# DEVELOPMENT-BOARD-PIC16F887.net
KiCad netlist of a schematic drawn in EasyEDA Pro
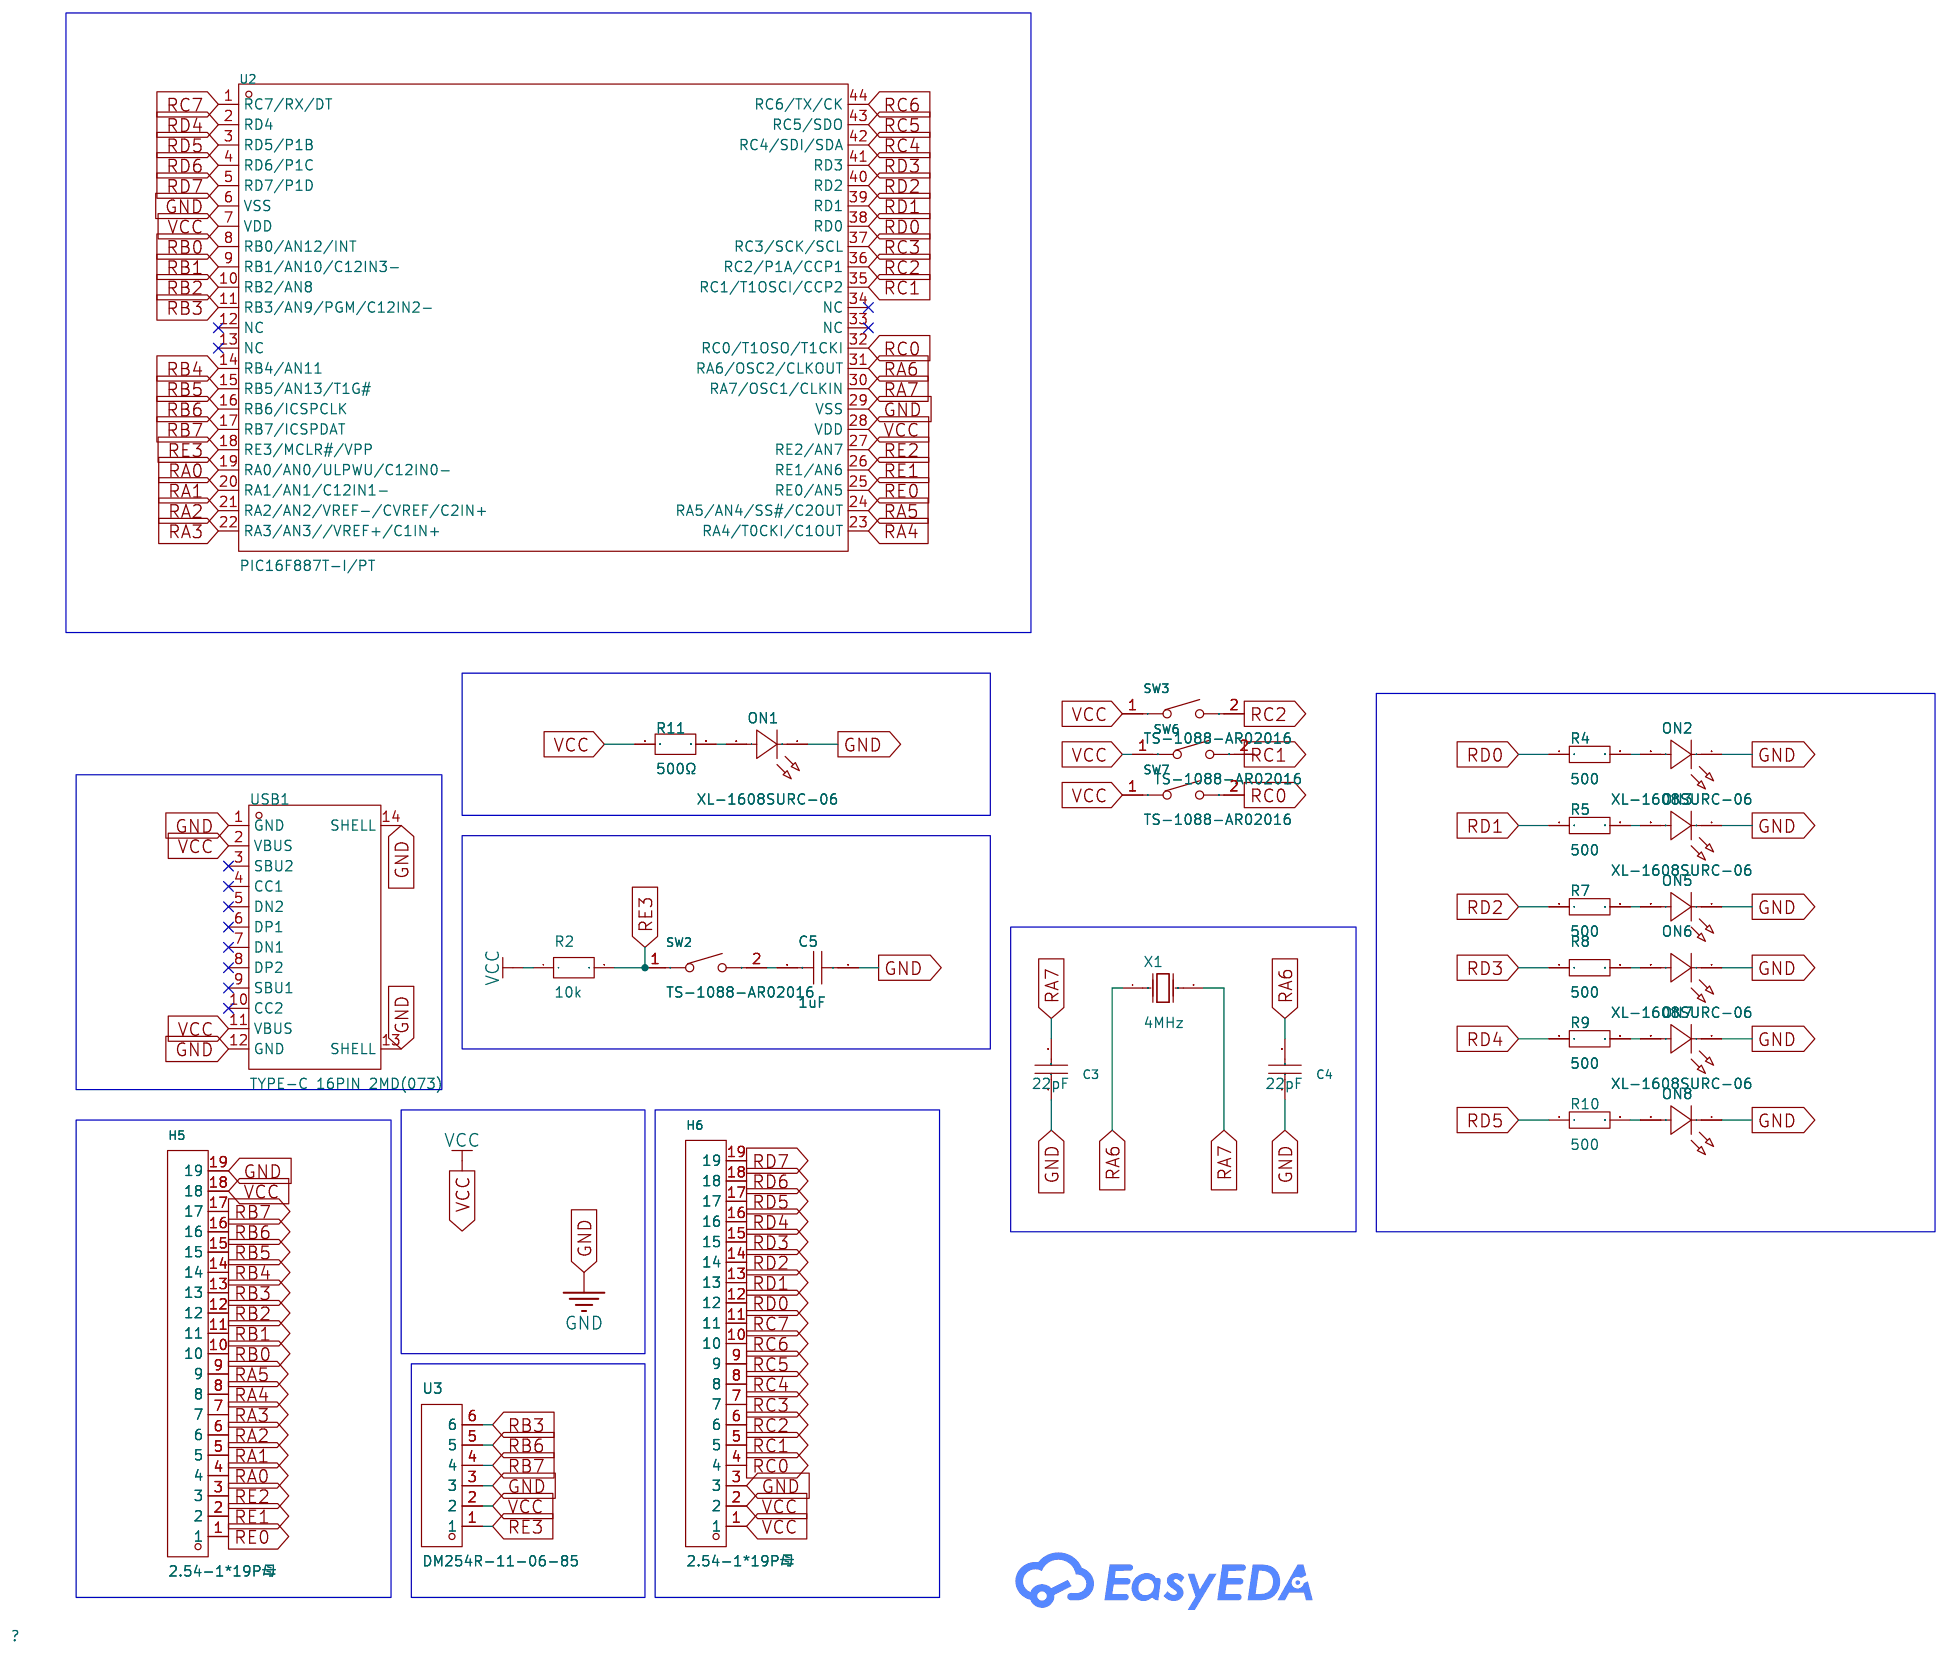
[diagram p0: schematic sheet]

(export (version "E")
  (design (tool "Eeschema 10.0.6"))
  (components
    (comp (ref "C3")
      (value "22pF")
      (footprint "easyedapro:C0402")
      (fields
        (field (name "Manufacturer Part") "CC0402JRNPO9BN150")
        (field (name "Manufacturer") "YAGEO(国巨)")
      )
      (libsource (lib "easyedapro") (part "CC0402JRNPO9BN150"))
    )
    (comp (ref "C4")
      (value "22pF")
      (footprint "easyedapro:C0402")
      (fields
        (field (name "Manufacturer Part") "CC0402JRNPO9BN150")
        (field (name "Manufacturer") "YAGEO(国巨)")
      )
      (libsource (lib "easyedapro") (part "CC0402JRNPO9BN150"))
    )
    (comp (ref "C5")
      (value "1uF")
      (footprint "easyedapro:C0603")
      (fields
        (field (name "Manufacturer Part") "CL10A105KB8NNNC")
        (field (name "Manufacturer") "SAMSUNG(三星)")
      )
      (libsource (lib "easyedapro") (part "CL10A105KB8NNNC"))
    )
    (comp (ref "H5")
      (value "2.54-1*19P母")
      (footprint "easyedapro:HDR-TH_19P-P2.54-V-F")
      (fields (field (name "Manufacturer") "BOOMELE(博穆精密)"))
      (libsource (lib "easyedapro") (part "2.54-1*19P母"))
    )
    (comp (ref "H6")
      (value "2.54-1*19P母")
      (footprint "easyedapro:HDR-TH_19P-P2.54-V-F")
      (fields (field (name "Manufacturer") "BOOMELE(博穆精密)"))
      (libsource (lib "easyedapro") (part "2.54-1*19P母"))
    )
    (comp (ref "ON1")
      (value "XL-1608SURC-06")
      (footprint "easyedapro:LED0603-RD_RED")
      (fields (field (name "Manufacturer") "XINGLIGHT(成兴光)"))
      (libsource (lib "easyedapro") (part "XL-1608SURC-06"))
    )
    (comp (ref "ON2")
      (value "XL-1608SURC-06")
      (footprint "easyedapro:LED0603-RD_RED")
      (fields (field (name "Manufacturer") "XINGLIGHT(成兴光)"))
      (libsource (lib "easyedapro") (part "XL-1608SURC-06"))
    )
    (comp (ref "ON3")
      (value "XL-1608SURC-06")
      (footprint "easyedapro:LED0603-RD_RED")
      (fields (field (name "Manufacturer") "XINGLIGHT(成兴光)"))
      (libsource (lib "easyedapro") (part "XL-1608SURC-06"))
    )
    (comp (ref "ON5")
      (value "XL-1608SURC-06")
      (footprint "easyedapro:LED0603-RD_RED")
      (fields (field (name "Manufacturer") "XINGLIGHT(成兴光)"))
      (libsource (lib "easyedapro") (part "XL-1608SURC-06"))
    )
    (comp (ref "ON6")
      (value "XL-1608SURC-06")
      (footprint "easyedapro:LED0603-RD_RED")
      (fields (field (name "Manufacturer") "XINGLIGHT(成兴光)"))
      (libsource (lib "easyedapro") (part "XL-1608SURC-06"))
    )
    (comp (ref "ON7")
      (value "XL-1608SURC-06")
      (footprint "easyedapro:LED0603-RD_RED")
      (fields (field (name "Manufacturer") "XINGLIGHT(成兴光)"))
      (libsource (lib "easyedapro") (part "XL-1608SURC-06"))
    )
    (comp (ref "ON8")
      (value "XL-1608SURC-06")
      (footprint "easyedapro:LED0603-RD_RED")
      (fields (field (name "Manufacturer") "XINGLIGHT(成兴光)"))
      (libsource (lib "easyedapro") (part "XL-1608SURC-06"))
    )
    (comp (ref "R2")
      (value "10k")
      (footprint "easyedapro:R0805")
      (fields (field (name "Manufacturer Part") "ARG05BTC5001N") (field (name "Manufacturer") "Viking(光颉)"))
      (libsource (lib "easyedapro") (part "ARG05BTC5001N"))
    )
    (comp (ref "R4")
      (value "500")
      (footprint "easyedapro:R0603")
      (fields
        (field (name "Manufacturer Part") "0603WAF3300T5E")
        (field (name "Manufacturer") "UNI-ROYAL(厚声)")
      )
      (libsource (lib "easyedapro") (part "0603WAF3300T5E"))
    )
    (comp (ref "R5")
      (value "500")
      (footprint "easyedapro:R0603")
      (fields
        (field (name "Manufacturer Part") "0603WAF3300T5E")
        (field (name "Manufacturer") "UNI-ROYAL(厚声)")
      )
      (libsource (lib "easyedapro") (part "0603WAF3300T5E"))
    )
    (comp (ref "R7")
      (value "500")
      (footprint "easyedapro:R0603")
      (fields
        (field (name "Manufacturer Part") "0603WAF3300T5E")
        (field (name "Manufacturer") "UNI-ROYAL(厚声)")
      )
      (libsource (lib "easyedapro") (part "0603WAF3300T5E"))
    )
    (comp (ref "R8")
      (value "500")
      (footprint "easyedapro:R0603")
      (fields
        (field (name "Manufacturer Part") "0603WAF3300T5E")
        (field (name "Manufacturer") "UNI-ROYAL(厚声)")
      )
      (libsource (lib "easyedapro") (part "0603WAF3300T5E"))
    )
    (comp (ref "R9")
      (value "500")
      (footprint "easyedapro:R0603")
      (fields
        (field (name "Manufacturer Part") "0603WAF3300T5E")
        (field (name "Manufacturer") "UNI-ROYAL(厚声)")
      )
      (libsource (lib "easyedapro") (part "0603WAF3300T5E"))
    )
    (comp (ref "R10")
      (value "500")
      (footprint "easyedapro:R0603")
      (fields
        (field (name "Manufacturer Part") "0603WAF3300T5E")
        (field (name "Manufacturer") "UNI-ROYAL(厚声)")
      )
      (libsource (lib "easyedapro") (part "0603WAF3300T5E"))
    )
    (comp (ref "R11")
      (value "500Ω")
      (footprint "easyedapro:R0805")
      (fields (field (name "Manufacturer Part") "ARG05FTC5000") (field (name "Manufacturer") "Viking(光颉)"))
      (libsource (lib "easyedapro") (part "ARG05FTC5000"))
    )
    (comp (ref "SW2")
      (value "TS-1088-AR02016")
      (footprint "easyedapro:SW-SMD_L3.9-W3.0-P4.45")
      (fields (field (name "Manufacturer") "XUNPU(讯普)"))
      (libsource (lib "easyedapro") (part "TS-1088-AR02016"))
    )
    (comp (ref "SW3")
      (value "TS-1088-AR02016")
      (footprint "easyedapro:SW-SMD_L3.9-W3.0-P4.45")
      (fields (field (name "Manufacturer") "XUNPU(讯普)"))
      (libsource (lib "easyedapro") (part "TS-1088-AR02016"))
    )
    (comp (ref "SW6")
      (value "TS-1088-AR02016")
      (footprint "easyedapro:SW-SMD_L3.9-W3.0-P4.45")
      (fields (field (name "Manufacturer") "XUNPU(讯普)"))
      (libsource (lib "easyedapro") (part "TS-1088-AR02016"))
    )
    (comp (ref "SW7")
      (value "TS-1088-AR02016")
      (footprint "easyedapro:SW-SMD_L3.9-W3.0-P4.45")
      (fields (field (name "Manufacturer") "XUNPU(讯普)"))
      (libsource (lib "easyedapro") (part "TS-1088-AR02016"))
    )
    (comp (ref "U2")
      (value "PIC16F887T-I/PT")
      (footprint "easyedapro:TQFP-44_L10.0-W10.0-P0.80-LS12.0-BL")
      (fields (field (name "Manufacturer") "MICROCHIP(美国微芯)"))
      (libsource (lib "easyedapro") (part "PIC16F887T-I/PT"))
    )
    (comp (ref "U3")
      (value "DM254R-11-06-85")
      (footprint "easyedapro:HDR-TH_6P-P2.54-V-F")
      (fields (field (name "Manufacturer") "DEALON(德艺隆)"))
      (libsource (lib "easyedapro") (part "DM254R-11-06-85"))
    )
    (comp (ref "USB1")
      (value "TYPE-C 16PIN 2MD(073)")
      (footprint "easyedapro:USB-C-SMD_TYPE-C-6PIN-2MD-073")
      (fields (field (name "Manufacturer") "SHOU HAN(首韩)"))
      (libsource (lib "easyedapro") (part "TYPE-C 16PIN 2MD(073)"))
    )
    (comp (ref "X1")
      (value "4MHz")
      (footprint "easyedapro:HC-49S_L11.4-W4.5-LS12.5")
      (fields (field (name "Manufacturer Part") "X49SM4MSD2SC") (field (name "Manufacturer") "YXC(扬兴晶振)"))
      (libsource (lib "easyedapro") (part "X49SM4MSD2SC"))
    )
  )
  (nets
    (net (code "1") (name "GND") (class "Default")
      (node (ref "C3") (pin "1") (pinfunction "1_1") (pintype "input"))
      (node (ref "C4") (pin "1") (pinfunction "1_1") (pintype "input"))
      (node (ref "C5") (pin "1") (pinfunction "1_1") (pintype "unspecified"))
      (node (ref "H5") (pin "19") (pinfunction "19_19") (pintype "input"))
      (node (ref "H6") (pin "3") (pinfunction "3_3") (pintype "input"))
      (node (ref "ON1") (pin "1") (pinfunction "K_1") (pintype "unspecified"))
      (node (ref "ON2") (pin "1") (pinfunction "K_1") (pintype "unspecified"))
      (node (ref "ON3") (pin "1") (pinfunction "K_1") (pintype "unspecified"))
      (node (ref "ON5") (pin "1") (pinfunction "K_1") (pintype "unspecified"))
      (node (ref "ON6") (pin "1") (pinfunction "K_1") (pintype "unspecified"))
      (node (ref "ON7") (pin "1") (pinfunction "K_1") (pintype "unspecified"))
      (node (ref "ON8") (pin "1") (pinfunction "K_1") (pintype "unspecified"))
      (node (ref "U2") (pin "29") (pinfunction "VSS_29") (pintype "input"))
      (node (ref "U2") (pin "6") (pinfunction "VSS_6") (pintype "input"))
      (node (ref "U3") (pin "3") (pinfunction "3_3") (pintype "unspecified"))
      (node (ref "USB1") (pin "1") (pinfunction "GND_1") (pintype "unspecified"))
      (node (ref "USB1") (pin "12") (pinfunction "GND_12") (pintype "unspecified"))
      (node (ref "USB1") (pin "13") (pinfunction "SHELL_13") (pintype "unspecified"))
      (node (ref "USB1") (pin "14") (pinfunction "SHELL_14") (pintype "unspecified"))
    )
    (net (code "2") (name "Net-(C5-Pad2)") (class "Default")
      (node (ref "C5") (pin "2") (pinfunction "2_2") (pintype "unspecified"))
      (node (ref "SW2") (pin "2") (pinfunction "2_2") (pintype "input"))
    )
    (net (code "3") (name "Net-(ON1-A)") (class "Default")
      (node (ref "ON1") (pin "2") (pinfunction "A_2") (pintype "unspecified"))
      (node (ref "R11") (pin "2") (pinfunction "2_2") (pintype "unspecified"))
    )
    (net (code "4") (name "Net-(ON2-A)") (class "Default")
      (node (ref "ON2") (pin "2") (pinfunction "A_2") (pintype "unspecified"))
      (node (ref "R4") (pin "2") (pinfunction "2_2") (pintype "input"))
    )
    (net (code "5") (name "Net-(ON3-A)") (class "Default")
      (node (ref "ON3") (pin "2") (pinfunction "A_2") (pintype "unspecified"))
      (node (ref "R5") (pin "2") (pinfunction "2_2") (pintype "input"))
    )
    (net (code "6") (name "Net-(ON5-A)") (class "Default")
      (node (ref "ON5") (pin "2") (pinfunction "A_2") (pintype "unspecified"))
      (node (ref "R7") (pin "2") (pinfunction "2_2") (pintype "input"))
    )
    (net (code "7") (name "Net-(ON6-A)") (class "Default")
      (node (ref "ON6") (pin "2") (pinfunction "A_2") (pintype "unspecified"))
      (node (ref "R8") (pin "2") (pinfunction "2_2") (pintype "input"))
    )
    (net (code "8") (name "Net-(ON7-A)") (class "Default")
      (node (ref "ON7") (pin "2") (pinfunction "A_2") (pintype "unspecified"))
      (node (ref "R9") (pin "2") (pinfunction "2_2") (pintype "input"))
    )
    (net (code "9") (name "Net-(ON8-A)") (class "Default")
      (node (ref "ON8") (pin "2") (pinfunction "A_2") (pintype "unspecified"))
      (node (ref "R10") (pin "2") (pinfunction "2_2") (pintype "input"))
    )
    (net (code "10") (name "RA0") (class "Default")
      (node (ref "H5") (pin "4") (pinfunction "4_4") (pintype "input"))
      (node (ref "U2") (pin "19") (pinfunction "RA0/AN0/ULPWU/C12IN0-_19") (pintype "input"))
    )
    (net (code "11") (name "RA1") (class "Default")
      (node (ref "H5") (pin "5") (pinfunction "5_5") (pintype "input"))
      (node (ref "U2") (pin "20") (pinfunction "RA1/AN1/C12IN1-_20") (pintype "input"))
    )
    (net (code "12") (name "RA2") (class "Default")
      (node (ref "H5") (pin "6") (pinfunction "6_6") (pintype "input"))
      (node (ref "U2") (pin "21") (pinfunction "RA2/AN2/VREF-/CVREF/C2IN+_21") (pintype "input"))
    )
    (net (code "13") (name "RA3") (class "Default")
      (node (ref "H5") (pin "7") (pinfunction "7_7") (pintype "input"))
      (node (ref "U2") (pin "22") (pinfunction "RA3/AN3//VREF+/C1IN+_22") (pintype "input"))
    )
    (net (code "14") (name "RA4") (class "Default")
      (node (ref "H5") (pin "8") (pinfunction "8_8") (pintype "input"))
      (node (ref "U2") (pin "23") (pinfunction "RA4/T0CKI/C1OUT_23") (pintype "input"))
    )
    (net (code "15") (name "RA5") (class "Default")
      (node (ref "H5") (pin "9") (pinfunction "9_9") (pintype "input"))
      (node (ref "U2") (pin "24") (pinfunction "RA5/AN4/SS#/C2OUT_24") (pintype "input"))
    )
    (net (code "16") (name "RA6") (class "Default")
      (node (ref "C4") (pin "2") (pinfunction "2_2") (pintype "input"))
      (node (ref "U2") (pin "31") (pinfunction "RA6/OSC2/CLKOUT_31") (pintype "input"))
      (node (ref "X1") (pin "1") (pinfunction "OSC1_1") (pintype "input"))
    )
    (net (code "17") (name "RA7") (class "Default")
      (node (ref "C3") (pin "2") (pinfunction "2_2") (pintype "input"))
      (node (ref "U2") (pin "30") (pinfunction "RA7/OSC1/CLKIN_30") (pintype "input"))
      (node (ref "X1") (pin "2") (pinfunction "OSC2_2") (pintype "input"))
    )
    (net (code "18") (name "RB0") (class "Default")
      (node (ref "H5") (pin "10") (pinfunction "10_10") (pintype "input"))
      (node (ref "U2") (pin "8") (pinfunction "RB0/AN12/INT_8") (pintype "input"))
    )
    (net (code "19") (name "RB1") (class "Default")
      (node (ref "H5") (pin "11") (pinfunction "11_11") (pintype "input"))
      (node (ref "U2") (pin "9") (pinfunction "RB1/AN10/C12IN3-_9") (pintype "input"))
    )
    (net (code "20") (name "RB2") (class "Default")
      (node (ref "H5") (pin "12") (pinfunction "12_12") (pintype "input"))
      (node (ref "U2") (pin "10") (pinfunction "RB2/AN8_10") (pintype "input"))
    )
    (net (code "21") (name "RB3") (class "Default")
      (node (ref "H5") (pin "13") (pinfunction "13_13") (pintype "input"))
      (node (ref "U2") (pin "11") (pinfunction "RB3/AN9/PGM/C12IN2-_11") (pintype "input"))
      (node (ref "U3") (pin "6") (pinfunction "6_6") (pintype "unspecified"))
    )
    (net (code "22") (name "RB4") (class "Default")
      (node (ref "H5") (pin "14") (pinfunction "14_14") (pintype "input"))
      (node (ref "U2") (pin "14") (pinfunction "RB4/AN11_14") (pintype "input"))
    )
    (net (code "23") (name "RB5") (class "Default")
      (node (ref "H5") (pin "15") (pinfunction "15_15") (pintype "input"))
      (node (ref "U2") (pin "15") (pinfunction "RB5/AN13/T1G#_15") (pintype "input"))
    )
    (net (code "24") (name "RB6") (class "Default")
      (node (ref "H5") (pin "16") (pinfunction "16_16") (pintype "input"))
      (node (ref "U2") (pin "16") (pinfunction "RB6/ICSPCLK_16") (pintype "input"))
      (node (ref "U3") (pin "5") (pinfunction "5_5") (pintype "unspecified"))
    )
    (net (code "25") (name "RB7") (class "Default")
      (node (ref "H5") (pin "17") (pinfunction "17_17") (pintype "input"))
      (node (ref "U2") (pin "17") (pinfunction "RB7/ICSPDAT_17") (pintype "input"))
      (node (ref "U3") (pin "4") (pinfunction "4_4") (pintype "unspecified"))
    )
    (net (code "26") (name "RC0") (class "Default")
      (node (ref "H6") (pin "4") (pinfunction "4_4") (pintype "input"))
      (node (ref "SW7") (pin "2") (pinfunction "2_2") (pintype "input"))
      (node (ref "U2") (pin "32") (pinfunction "RC0/T1OSO/T1CKI_32") (pintype "input"))
    )
    (net (code "27") (name "RC1") (class "Default")
      (node (ref "H6") (pin "5") (pinfunction "5_5") (pintype "input"))
      (node (ref "SW6") (pin "2") (pinfunction "2_2") (pintype "input"))
      (node (ref "U2") (pin "35") (pinfunction "RC1/T1OSCI/CCP2_35") (pintype "input"))
    )
    (net (code "28") (name "RC2") (class "Default")
      (node (ref "H6") (pin "6") (pinfunction "6_6") (pintype "input"))
      (node (ref "SW3") (pin "2") (pinfunction "2_2") (pintype "input"))
      (node (ref "U2") (pin "36") (pinfunction "RC2/P1A/CCP1_36") (pintype "input"))
    )
    (net (code "29") (name "RC3") (class "Default")
      (node (ref "H6") (pin "7") (pinfunction "7_7") (pintype "input"))
      (node (ref "U2") (pin "37") (pinfunction "RC3/SCK/SCL_37") (pintype "input"))
    )
    (net (code "30") (name "RC4") (class "Default")
      (node (ref "H6") (pin "8") (pinfunction "8_8") (pintype "input"))
      (node (ref "U2") (pin "42") (pinfunction "RC4/SDI/SDA_42") (pintype "input"))
    )
    (net (code "31") (name "RC5") (class "Default")
      (node (ref "H6") (pin "9") (pinfunction "9_9") (pintype "input"))
      (node (ref "U2") (pin "43") (pinfunction "RC5/SDO_43") (pintype "input"))
    )
    (net (code "32") (name "RC6") (class "Default")
      (node (ref "H6") (pin "10") (pinfunction "10_10") (pintype "input"))
      (node (ref "U2") (pin "44") (pinfunction "RC6/TX/CK_44") (pintype "input"))
    )
    (net (code "33") (name "RC7") (class "Default")
      (node (ref "H6") (pin "11") (pinfunction "11_11") (pintype "input"))
      (node (ref "U2") (pin "1") (pinfunction "RC7/RX/DT_1") (pintype "input"))
    )
    (net (code "34") (name "RD0") (class "Default")
      (node (ref "H6") (pin "12") (pinfunction "12_12") (pintype "input"))
      (node (ref "R4") (pin "1") (pinfunction "1_1") (pintype "input"))
      (node (ref "U2") (pin "38") (pinfunction "RD0_38") (pintype "input"))
    )
    (net (code "35") (name "RD1") (class "Default")
      (node (ref "H6") (pin "13") (pinfunction "13_13") (pintype "input"))
      (node (ref "R5") (pin "1") (pinfunction "1_1") (pintype "input"))
      (node (ref "U2") (pin "39") (pinfunction "RD1_39") (pintype "input"))
    )
    (net (code "36") (name "RD2") (class "Default")
      (node (ref "H6") (pin "14") (pinfunction "14_14") (pintype "input"))
      (node (ref "R7") (pin "1") (pinfunction "1_1") (pintype "input"))
      (node (ref "U2") (pin "40") (pinfunction "RD2_40") (pintype "input"))
    )
    (net (code "37") (name "RD3") (class "Default")
      (node (ref "H6") (pin "15") (pinfunction "15_15") (pintype "input"))
      (node (ref "R8") (pin "1") (pinfunction "1_1") (pintype "input"))
      (node (ref "U2") (pin "41") (pinfunction "RD3_41") (pintype "input"))
    )
    (net (code "38") (name "RD4") (class "Default")
      (node (ref "H6") (pin "16") (pinfunction "16_16") (pintype "input"))
      (node (ref "R9") (pin "1") (pinfunction "1_1") (pintype "input"))
      (node (ref "U2") (pin "2") (pinfunction "RD4_2") (pintype "input"))
    )
    (net (code "39") (name "RD5") (class "Default")
      (node (ref "H6") (pin "17") (pinfunction "17_17") (pintype "input"))
      (node (ref "R10") (pin "1") (pinfunction "1_1") (pintype "input"))
      (node (ref "U2") (pin "3") (pinfunction "RD5/P1B_3") (pintype "input"))
    )
    (net (code "40") (name "RD6") (class "Default")
      (node (ref "H6") (pin "18") (pinfunction "18_18") (pintype "input"))
      (node (ref "U2") (pin "4") (pinfunction "RD6/P1C_4") (pintype "input"))
    )
    (net (code "41") (name "RD7") (class "Default")
      (node (ref "H6") (pin "19") (pinfunction "19_19") (pintype "input"))
      (node (ref "U2") (pin "5") (pinfunction "RD7/P1D_5") (pintype "input"))
    )
    (net (code "42") (name "RE0") (class "Default")
      (node (ref "H5") (pin "1") (pinfunction "1_1") (pintype "input"))
      (node (ref "U2") (pin "25") (pinfunction "RE0/AN5_25") (pintype "input"))
    )
    (net (code "43") (name "RE1") (class "Default")
      (node (ref "H5") (pin "2") (pinfunction "2_2") (pintype "input"))
      (node (ref "U2") (pin "26") (pinfunction "RE1/AN6_26") (pintype "input"))
    )
    (net (code "44") (name "RE2") (class "Default")
      (node (ref "H5") (pin "3") (pinfunction "3_3") (pintype "input"))
      (node (ref "U2") (pin "27") (pinfunction "RE2/AN7_27") (pintype "input"))
    )
    (net (code "45") (name "RE3") (class "Default")
      (node (ref "R2") (pin "2") (pinfunction "2_2") (pintype "unspecified"))
      (node (ref "SW2") (pin "1") (pinfunction "1_1") (pintype "input"))
      (node (ref "U2") (pin "18") (pinfunction "RE3/MCLR#/VPP_18") (pintype "input"))
      (node (ref "U3") (pin "1") (pinfunction "1_1") (pintype "unspecified"))
    )
    (net (code "46") (name "VCC") (class "Default")
      (node (ref "H5") (pin "18") (pinfunction "18_18") (pintype "input"))
      (node (ref "H6") (pin "1") (pinfunction "1_1") (pintype "input"))
      (node (ref "H6") (pin "2") (pinfunction "2_2") (pintype "input"))
      (node (ref "R11") (pin "1") (pinfunction "1_1") (pintype "unspecified"))
      (node (ref "R2") (pin "1") (pinfunction "1_1") (pintype "unspecified"))
      (node (ref "SW3") (pin "1") (pinfunction "1_1") (pintype "input"))
      (node (ref "SW6") (pin "1") (pinfunction "1_1") (pintype "input"))
      (node (ref "SW7") (pin "1") (pinfunction "1_1") (pintype "input"))
      (node (ref "U2") (pin "28") (pinfunction "VDD_28") (pintype "input"))
      (node (ref "U2") (pin "7") (pinfunction "VDD_7") (pintype "input"))
      (node (ref "U3") (pin "2") (pinfunction "2_2") (pintype "unspecified"))
      (node (ref "USB1") (pin "11") (pinfunction "VBUS_11") (pintype "unspecified"))
      (node (ref "USB1") (pin "2") (pinfunction "VBUS_2") (pintype "unspecified"))
    )
    (net (code "47") (name "unconnected-(U2-NC-Pad12)") (class "Default")
      (node (ref "U2") (pin "12") (pinfunction "NC_12") (pintype "input+no_connect"))
    )
    (net (code "48") (name "unconnected-(U2-NC-Pad13)") (class "Default")
      (node (ref "U2") (pin "13") (pinfunction "NC_13") (pintype "input+no_connect"))
    )
    (net (code "49") (name "unconnected-(U2-NC-Pad33)") (class "Default")
      (node (ref "U2") (pin "33") (pinfunction "NC_33") (pintype "input+no_connect"))
    )
    (net (code "50") (name "unconnected-(U2-NC-Pad34)") (class "Default")
      (node (ref "U2") (pin "34") (pinfunction "NC_34") (pintype "input+no_connect"))
    )
    (net (code "51") (name "unconnected-(USB1-CC1-Pad4)") (class "Default")
      (node (ref "USB1") (pin "4") (pinfunction "CC1_4") (pintype "unspecified+no_connect"))
    )
    (net (code "52") (name "unconnected-(USB1-CC2-Pad10)") (class "Default")
      (node (ref "USB1") (pin "10") (pinfunction "CC2_10") (pintype "unspecified+no_connect"))
    )
    (net (code "53") (name "unconnected-(USB1-DN1-Pad7)") (class "Default")
      (node (ref "USB1") (pin "7") (pinfunction "DN1_7") (pintype "unspecified+no_connect"))
    )
    (net (code "54") (name "unconnected-(USB1-DN2-Pad5)") (class "Default")
      (node (ref "USB1") (pin "5") (pinfunction "DN2_5") (pintype "unspecified+no_connect"))
    )
    (net (code "55") (name "unconnected-(USB1-DP1-Pad6)") (class "Default")
      (node (ref "USB1") (pin "6") (pinfunction "DP1_6") (pintype "unspecified+no_connect"))
    )
    (net (code "56") (name "unconnected-(USB1-DP2-Pad8)") (class "Default")
      (node (ref "USB1") (pin "8") (pinfunction "DP2_8") (pintype "unspecified+no_connect"))
    )
    (net (code "57") (name "unconnected-(USB1-SBU1-Pad9)") (class "Default")
      (node (ref "USB1") (pin "9") (pinfunction "SBU1_9") (pintype "unspecified+no_connect"))
    )
    (net (code "58") (name "unconnected-(USB1-SBU2-Pad3)") (class "Default")
      (node (ref "USB1") (pin "3") (pinfunction "SBU2_3") (pintype "unspecified+no_connect"))
    )
  )
)
